# N_FET.net
KiCad netlist of a schematic drawn in Altium Designer
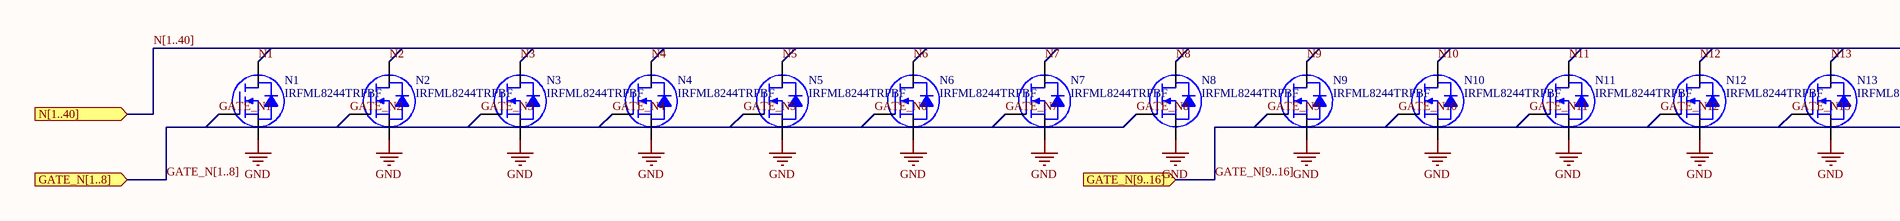
[diagram p0: N_FET.SchDoc, left]
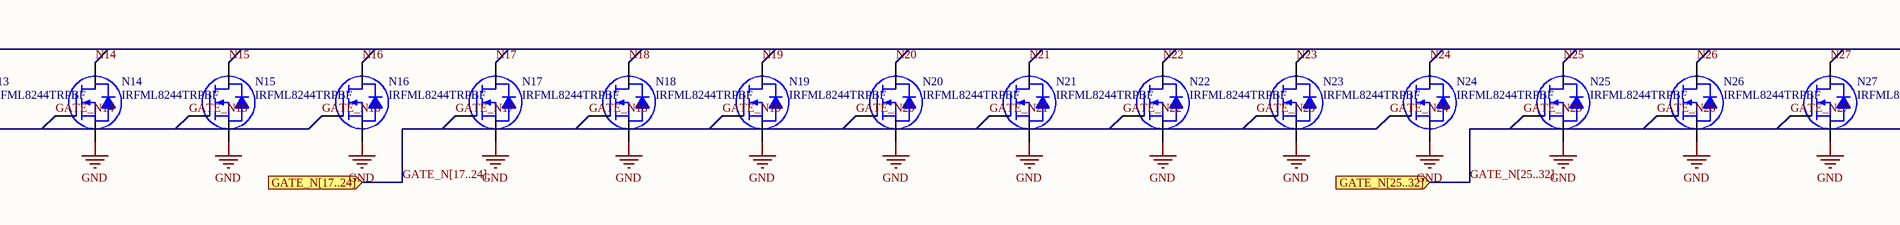
[diagram p1: N_FET.SchDoc, middle]
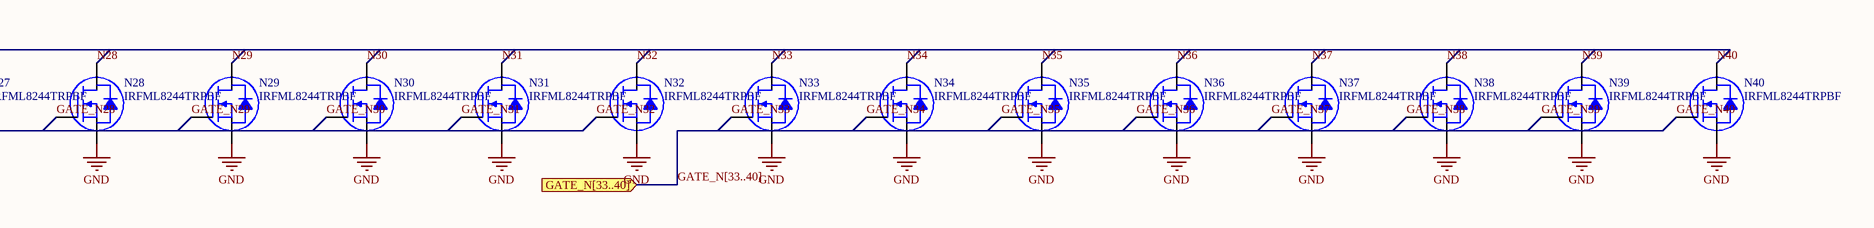
[diagram p2: N_FET.SchDoc, right]

(export (version "E")
  (design (tool "Eeschema 10.0.6"))
  (components
    (comp (ref "N1")
      (value "IRFML8244TRPBF")
      (footprint "INFINEON SOT-23-3")
      (description "MOSFET N-CH 25V 5.8A SOT23")
      (fields (field (name "MANUFACTURER") "Infineon Technologies"))
      (libsource (lib "Celestial Library Database") (part "INFINEON MOSFET N-CH SOT-23-3"))
    )
    (comp (ref "N2")
      (value "IRFML8244TRPBF")
      (footprint "INFINEON SOT-23-3")
      (description "MOSFET N-CH 25V 5.8A SOT23")
      (fields (field (name "MANUFACTURER") "Infineon Technologies"))
      (libsource (lib "Celestial Library Database") (part "INFINEON MOSFET N-CH SOT-23-3"))
    )
    (comp (ref "N3")
      (value "IRFML8244TRPBF")
      (footprint "INFINEON SOT-23-3")
      (description "MOSFET N-CH 25V 5.8A SOT23")
      (fields (field (name "MANUFACTURER") "Infineon Technologies"))
      (libsource (lib "Celestial Library Database") (part "INFINEON MOSFET N-CH SOT-23-3"))
    )
    (comp (ref "N4")
      (value "IRFML8244TRPBF")
      (footprint "INFINEON SOT-23-3")
      (description "MOSFET N-CH 25V 5.8A SOT23")
      (fields (field (name "MANUFACTURER") "Infineon Technologies"))
      (libsource (lib "Celestial Library Database") (part "INFINEON MOSFET N-CH SOT-23-3"))
    )
    (comp (ref "N5")
      (value "IRFML8244TRPBF")
      (footprint "INFINEON SOT-23-3")
      (description "MOSFET N-CH 25V 5.8A SOT23")
      (fields (field (name "MANUFACTURER") "Infineon Technologies"))
      (libsource (lib "Celestial Library Database") (part "INFINEON MOSFET N-CH SOT-23-3"))
    )
    (comp (ref "N6")
      (value "IRFML8244TRPBF")
      (footprint "INFINEON SOT-23-3")
      (description "MOSFET N-CH 25V 5.8A SOT23")
      (fields (field (name "MANUFACTURER") "Infineon Technologies"))
      (libsource (lib "Celestial Library Database") (part "INFINEON MOSFET N-CH SOT-23-3"))
    )
    (comp (ref "N7")
      (value "IRFML8244TRPBF")
      (footprint "INFINEON SOT-23-3")
      (description "MOSFET N-CH 25V 5.8A SOT23")
      (fields (field (name "MANUFACTURER") "Infineon Technologies"))
      (libsource (lib "Celestial Library Database") (part "INFINEON MOSFET N-CH SOT-23-3"))
    )
    (comp (ref "N8")
      (value "IRFML8244TRPBF")
      (footprint "INFINEON SOT-23-3")
      (description "MOSFET N-CH 25V 5.8A SOT23")
      (fields (field (name "MANUFACTURER") "Infineon Technologies"))
      (libsource (lib "Celestial Library Database") (part "INFINEON MOSFET N-CH SOT-23-3"))
    )
    (comp (ref "N9")
      (value "IRFML8244TRPBF")
      (footprint "INFINEON SOT-23-3")
      (description "MOSFET N-CH 25V 5.8A SOT23")
      (fields (field (name "MANUFACTURER") "Infineon Technologies"))
      (libsource (lib "Celestial Library Database") (part "INFINEON MOSFET N-CH SOT-23-3"))
    )
    (comp (ref "N10")
      (value "IRFML8244TRPBF")
      (footprint "INFINEON SOT-23-3")
      (description "MOSFET N-CH 25V 5.8A SOT23")
      (fields (field (name "MANUFACTURER") "Infineon Technologies"))
      (libsource (lib "Celestial Library Database") (part "INFINEON MOSFET N-CH SOT-23-3"))
    )
    (comp (ref "N11")
      (value "IRFML8244TRPBF")
      (footprint "INFINEON SOT-23-3")
      (description "MOSFET N-CH 25V 5.8A SOT23")
      (fields (field (name "MANUFACTURER") "Infineon Technologies"))
      (libsource (lib "Celestial Library Database") (part "INFINEON MOSFET N-CH SOT-23-3"))
    )
    (comp (ref "N12")
      (value "IRFML8244TRPBF")
      (footprint "INFINEON SOT-23-3")
      (description "MOSFET N-CH 25V 5.8A SOT23")
      (fields (field (name "MANUFACTURER") "Infineon Technologies"))
      (libsource (lib "Celestial Library Database") (part "INFINEON MOSFET N-CH SOT-23-3"))
    )
    (comp (ref "N13")
      (value "IRFML8244TRPBF")
      (footprint "INFINEON SOT-23-3")
      (description "MOSFET N-CH 25V 5.8A SOT23")
      (fields (field (name "MANUFACTURER") "Infineon Technologies"))
      (libsource (lib "Celestial Library Database") (part "INFINEON MOSFET N-CH SOT-23-3"))
    )
    (comp (ref "N14")
      (value "IRFML8244TRPBF")
      (footprint "INFINEON SOT-23-3")
      (description "MOSFET N-CH 25V 5.8A SOT23")
      (fields (field (name "MANUFACTURER") "Infineon Technologies"))
      (libsource (lib "Celestial Library Database") (part "INFINEON MOSFET N-CH SOT-23-3"))
    )
    (comp (ref "N15")
      (value "IRFML8244TRPBF")
      (footprint "INFINEON SOT-23-3")
      (description "MOSFET N-CH 25V 5.8A SOT23")
      (fields (field (name "MANUFACTURER") "Infineon Technologies"))
      (libsource (lib "Celestial Library Database") (part "INFINEON MOSFET N-CH SOT-23-3"))
    )
    (comp (ref "N16")
      (value "IRFML8244TRPBF")
      (footprint "INFINEON SOT-23-3")
      (description "MOSFET N-CH 25V 5.8A SOT23")
      (fields (field (name "MANUFACTURER") "Infineon Technologies"))
      (libsource (lib "Celestial Library Database") (part "INFINEON MOSFET N-CH SOT-23-3"))
    )
    (comp (ref "N17")
      (value "IRFML8244TRPBF")
      (footprint "INFINEON SOT-23-3")
      (description "MOSFET N-CH 25V 5.8A SOT23")
      (fields (field (name "MANUFACTURER") "Infineon Technologies"))
      (libsource (lib "Celestial Library Database") (part "INFINEON MOSFET N-CH SOT-23-3"))
    )
    (comp (ref "N18")
      (value "IRFML8244TRPBF")
      (footprint "INFINEON SOT-23-3")
      (description "MOSFET N-CH 25V 5.8A SOT23")
      (fields (field (name "MANUFACTURER") "Infineon Technologies"))
      (libsource (lib "Celestial Library Database") (part "INFINEON MOSFET N-CH SOT-23-3"))
    )
    (comp (ref "N19")
      (value "IRFML8244TRPBF")
      (footprint "INFINEON SOT-23-3")
      (description "MOSFET N-CH 25V 5.8A SOT23")
      (fields (field (name "MANUFACTURER") "Infineon Technologies"))
      (libsource (lib "Celestial Library Database") (part "INFINEON MOSFET N-CH SOT-23-3"))
    )
    (comp (ref "N20")
      (value "IRFML8244TRPBF")
      (footprint "INFINEON SOT-23-3")
      (description "MOSFET N-CH 25V 5.8A SOT23")
      (fields (field (name "MANUFACTURER") "Infineon Technologies"))
      (libsource (lib "Celestial Library Database") (part "INFINEON MOSFET N-CH SOT-23-3"))
    )
    (comp (ref "N21")
      (value "IRFML8244TRPBF")
      (footprint "INFINEON SOT-23-3")
      (description "MOSFET N-CH 25V 5.8A SOT23")
      (fields (field (name "MANUFACTURER") "Infineon Technologies"))
      (libsource (lib "Celestial Library Database") (part "INFINEON MOSFET N-CH SOT-23-3"))
    )
    (comp (ref "N22")
      (value "IRFML8244TRPBF")
      (footprint "INFINEON SOT-23-3")
      (description "MOSFET N-CH 25V 5.8A SOT23")
      (fields (field (name "MANUFACTURER") "Infineon Technologies"))
      (libsource (lib "Celestial Library Database") (part "INFINEON MOSFET N-CH SOT-23-3"))
    )
    (comp (ref "N23")
      (value "IRFML8244TRPBF")
      (footprint "INFINEON SOT-23-3")
      (description "MOSFET N-CH 25V 5.8A SOT23")
      (fields (field (name "MANUFACTURER") "Infineon Technologies"))
      (libsource (lib "Celestial Library Database") (part "INFINEON MOSFET N-CH SOT-23-3"))
    )
    (comp (ref "N24")
      (value "IRFML8244TRPBF")
      (footprint "INFINEON SOT-23-3")
      (description "MOSFET N-CH 25V 5.8A SOT23")
      (fields (field (name "MANUFACTURER") "Infineon Technologies"))
      (libsource (lib "Celestial Library Database") (part "INFINEON MOSFET N-CH SOT-23-3"))
    )
    (comp (ref "N25")
      (value "IRFML8244TRPBF")
      (footprint "INFINEON SOT-23-3")
      (description "MOSFET N-CH 25V 5.8A SOT23")
      (fields (field (name "MANUFACTURER") "Infineon Technologies"))
      (libsource (lib "Celestial Library Database") (part "INFINEON MOSFET N-CH SOT-23-3"))
    )
    (comp (ref "N26")
      (value "IRFML8244TRPBF")
      (footprint "INFINEON SOT-23-3")
      (description "MOSFET N-CH 25V 5.8A SOT23")
      (fields (field (name "MANUFACTURER") "Infineon Technologies"))
      (libsource (lib "Celestial Library Database") (part "INFINEON MOSFET N-CH SOT-23-3"))
    )
    (comp (ref "N27")
      (value "IRFML8244TRPBF")
      (footprint "INFINEON SOT-23-3")
      (description "MOSFET N-CH 25V 5.8A SOT23")
      (fields (field (name "MANUFACTURER") "Infineon Technologies"))
      (libsource (lib "Celestial Library Database") (part "INFINEON MOSFET N-CH SOT-23-3"))
    )
    (comp (ref "N28")
      (value "IRFML8244TRPBF")
      (footprint "INFINEON SOT-23-3")
      (description "MOSFET N-CH 25V 5.8A SOT23")
      (fields (field (name "MANUFACTURER") "Infineon Technologies"))
      (libsource (lib "Celestial Library Database") (part "INFINEON MOSFET N-CH SOT-23-3"))
    )
    (comp (ref "N29")
      (value "IRFML8244TRPBF")
      (footprint "INFINEON SOT-23-3")
      (description "MOSFET N-CH 25V 5.8A SOT23")
      (fields (field (name "MANUFACTURER") "Infineon Technologies"))
      (libsource (lib "Celestial Library Database") (part "INFINEON MOSFET N-CH SOT-23-3"))
    )
    (comp (ref "N30")
      (value "IRFML8244TRPBF")
      (footprint "INFINEON SOT-23-3")
      (description "MOSFET N-CH 25V 5.8A SOT23")
      (fields (field (name "MANUFACTURER") "Infineon Technologies"))
      (libsource (lib "Celestial Library Database") (part "INFINEON MOSFET N-CH SOT-23-3"))
    )
    (comp (ref "N31")
      (value "IRFML8244TRPBF")
      (footprint "INFINEON SOT-23-3")
      (description "MOSFET N-CH 25V 5.8A SOT23")
      (fields (field (name "MANUFACTURER") "Infineon Technologies"))
      (libsource (lib "Celestial Library Database") (part "INFINEON MOSFET N-CH SOT-23-3"))
    )
    (comp (ref "N32")
      (value "IRFML8244TRPBF")
      (footprint "INFINEON SOT-23-3")
      (description "MOSFET N-CH 25V 5.8A SOT23")
      (fields (field (name "MANUFACTURER") "Infineon Technologies"))
      (libsource (lib "Celestial Library Database") (part "INFINEON MOSFET N-CH SOT-23-3"))
    )
    (comp (ref "N33")
      (value "IRFML8244TRPBF")
      (footprint "INFINEON SOT-23-3")
      (description "MOSFET N-CH 25V 5.8A SOT23")
      (fields (field (name "MANUFACTURER") "Infineon Technologies"))
      (libsource (lib "Celestial Library Database") (part "INFINEON MOSFET N-CH SOT-23-3"))
    )
    (comp (ref "N34")
      (value "IRFML8244TRPBF")
      (footprint "INFINEON SOT-23-3")
      (description "MOSFET N-CH 25V 5.8A SOT23")
      (fields (field (name "MANUFACTURER") "Infineon Technologies"))
      (libsource (lib "Celestial Library Database") (part "INFINEON MOSFET N-CH SOT-23-3"))
    )
    (comp (ref "N35")
      (value "IRFML8244TRPBF")
      (footprint "INFINEON SOT-23-3")
      (description "MOSFET N-CH 25V 5.8A SOT23")
      (fields (field (name "MANUFACTURER") "Infineon Technologies"))
      (libsource (lib "Celestial Library Database") (part "INFINEON MOSFET N-CH SOT-23-3"))
    )
    (comp (ref "N36")
      (value "IRFML8244TRPBF")
      (footprint "INFINEON SOT-23-3")
      (description "MOSFET N-CH 25V 5.8A SOT23")
      (fields (field (name "MANUFACTURER") "Infineon Technologies"))
      (libsource (lib "Celestial Library Database") (part "INFINEON MOSFET N-CH SOT-23-3"))
    )
    (comp (ref "N37")
      (value "IRFML8244TRPBF")
      (footprint "INFINEON SOT-23-3")
      (description "MOSFET N-CH 25V 5.8A SOT23")
      (fields (field (name "MANUFACTURER") "Infineon Technologies"))
      (libsource (lib "Celestial Library Database") (part "INFINEON MOSFET N-CH SOT-23-3"))
    )
    (comp (ref "N38")
      (value "IRFML8244TRPBF")
      (footprint "INFINEON SOT-23-3")
      (description "MOSFET N-CH 25V 5.8A SOT23")
      (fields (field (name "MANUFACTURER") "Infineon Technologies"))
      (libsource (lib "Celestial Library Database") (part "INFINEON MOSFET N-CH SOT-23-3"))
    )
    (comp (ref "N39")
      (value "IRFML8244TRPBF")
      (footprint "INFINEON SOT-23-3")
      (description "MOSFET N-CH 25V 5.8A SOT23")
      (fields (field (name "MANUFACTURER") "Infineon Technologies"))
      (libsource (lib "Celestial Library Database") (part "INFINEON MOSFET N-CH SOT-23-3"))
    )
    (comp (ref "N40")
      (value "IRFML8244TRPBF")
      (footprint "INFINEON SOT-23-3")
      (description "MOSFET N-CH 25V 5.8A SOT23")
      (fields (field (name "MANUFACTURER") "Infineon Technologies"))
      (libsource (lib "Celestial Library Database") (part "INFINEON MOSFET N-CH SOT-23-3"))
    )
  )
  (nets
    (net (code "1") (name "/GATE_N1") (class "Default")
      (node (ref "N1") (pin "1") (pinfunction "G_1") (pintype "passive"))
    )
    (net (code "2") (name "/GATE_N2") (class "Default")
      (node (ref "N2") (pin "1") (pinfunction "G_1") (pintype "passive"))
    )
    (net (code "3") (name "/GATE_N3") (class "Default")
      (node (ref "N3") (pin "1") (pinfunction "G_1") (pintype "passive"))
    )
    (net (code "4") (name "/GATE_N4") (class "Default")
      (node (ref "N4") (pin "1") (pinfunction "G_1") (pintype "passive"))
    )
    (net (code "5") (name "/GATE_N5") (class "Default")
      (node (ref "N5") (pin "1") (pinfunction "G_1") (pintype "passive"))
    )
    (net (code "6") (name "/GATE_N6") (class "Default")
      (node (ref "N6") (pin "1") (pinfunction "G_1") (pintype "passive"))
    )
    (net (code "7") (name "/GATE_N7") (class "Default")
      (node (ref "N7") (pin "1") (pinfunction "G_1") (pintype "passive"))
    )
    (net (code "8") (name "/GATE_N8") (class "Default")
      (node (ref "N8") (pin "1") (pinfunction "G_1") (pintype "passive"))
    )
    (net (code "9") (name "/GATE_N9") (class "Default")
      (node (ref "N9") (pin "1") (pinfunction "G_1") (pintype "passive"))
    )
    (net (code "10") (name "/GATE_N10") (class "Default")
      (node (ref "N10") (pin "1") (pinfunction "G_1") (pintype "passive"))
    )
    (net (code "11") (name "/GATE_N11") (class "Default")
      (node (ref "N11") (pin "1") (pinfunction "G_1") (pintype "passive"))
    )
    (net (code "12") (name "/GATE_N12") (class "Default")
      (node (ref "N12") (pin "1") (pinfunction "G_1") (pintype "passive"))
    )
    (net (code "13") (name "/GATE_N13") (class "Default")
      (node (ref "N13") (pin "1") (pinfunction "G_1") (pintype "passive"))
    )
    (net (code "14") (name "/GATE_N14") (class "Default")
      (node (ref "N14") (pin "1") (pinfunction "G_1") (pintype "passive"))
    )
    (net (code "15") (name "/GATE_N15") (class "Default")
      (node (ref "N15") (pin "1") (pinfunction "G_1") (pintype "passive"))
    )
    (net (code "16") (name "/GATE_N16") (class "Default")
      (node (ref "N16") (pin "1") (pinfunction "G_1") (pintype "passive"))
    )
    (net (code "17") (name "/GATE_N17") (class "Default")
      (node (ref "N17") (pin "1") (pinfunction "G_1") (pintype "passive"))
    )
    (net (code "18") (name "/GATE_N18") (class "Default")
      (node (ref "N18") (pin "1") (pinfunction "G_1") (pintype "passive"))
    )
    (net (code "19") (name "/GATE_N19") (class "Default")
      (node (ref "N19") (pin "1") (pinfunction "G_1") (pintype "passive"))
    )
    (net (code "20") (name "/GATE_N20") (class "Default")
      (node (ref "N20") (pin "1") (pinfunction "G_1") (pintype "passive"))
    )
    (net (code "21") (name "/GATE_N21") (class "Default")
      (node (ref "N21") (pin "1") (pinfunction "G_1") (pintype "passive"))
    )
    (net (code "22") (name "/GATE_N22") (class "Default")
      (node (ref "N22") (pin "1") (pinfunction "G_1") (pintype "passive"))
    )
    (net (code "23") (name "/GATE_N23") (class "Default")
      (node (ref "N23") (pin "1") (pinfunction "G_1") (pintype "passive"))
    )
    (net (code "24") (name "/GATE_N24") (class "Default")
      (node (ref "N24") (pin "1") (pinfunction "G_1") (pintype "passive"))
    )
    (net (code "25") (name "/GATE_N25") (class "Default")
      (node (ref "N25") (pin "1") (pinfunction "G_1") (pintype "passive"))
    )
    (net (code "26") (name "/GATE_N26") (class "Default")
      (node (ref "N26") (pin "1") (pinfunction "G_1") (pintype "passive"))
    )
    (net (code "27") (name "/GATE_N27") (class "Default")
      (node (ref "N27") (pin "1") (pinfunction "G_1") (pintype "passive"))
    )
    (net (code "28") (name "/GATE_N28") (class "Default")
      (node (ref "N28") (pin "1") (pinfunction "G_1") (pintype "passive"))
    )
    (net (code "29") (name "/GATE_N29") (class "Default")
      (node (ref "N29") (pin "1") (pinfunction "G_1") (pintype "passive"))
    )
    (net (code "30") (name "/GATE_N30") (class "Default")
      (node (ref "N30") (pin "1") (pinfunction "G_1") (pintype "passive"))
    )
    (net (code "31") (name "/GATE_N31") (class "Default")
      (node (ref "N31") (pin "1") (pinfunction "G_1") (pintype "passive"))
    )
    (net (code "32") (name "/GATE_N32") (class "Default")
      (node (ref "N32") (pin "1") (pinfunction "G_1") (pintype "passive"))
    )
    (net (code "33") (name "/GATE_N33") (class "Default")
      (node (ref "N33") (pin "1") (pinfunction "G_1") (pintype "passive"))
    )
    (net (code "34") (name "/GATE_N34") (class "Default")
      (node (ref "N34") (pin "1") (pinfunction "G_1") (pintype "passive"))
    )
    (net (code "35") (name "/GATE_N35") (class "Default")
      (node (ref "N35") (pin "1") (pinfunction "G_1") (pintype "passive"))
    )
    (net (code "36") (name "/GATE_N36") (class "Default")
      (node (ref "N36") (pin "1") (pinfunction "G_1") (pintype "passive"))
    )
    (net (code "37") (name "/GATE_N37") (class "Default")
      (node (ref "N37") (pin "1") (pinfunction "G_1") (pintype "passive"))
    )
    (net (code "38") (name "/GATE_N38") (class "Default")
      (node (ref "N38") (pin "1") (pinfunction "G_1") (pintype "passive"))
    )
    (net (code "39") (name "/GATE_N39") (class "Default")
      (node (ref "N39") (pin "1") (pinfunction "G_1") (pintype "passive"))
    )
    (net (code "40") (name "/GATE_N40") (class "Default")
      (node (ref "N40") (pin "1") (pinfunction "G_1") (pintype "passive"))
    )
    (net (code "46") (name "/N1") (class "Default")
      (node (ref "N1") (pin "2") (pinfunction "D_2") (pintype "passive"))
    )
    (net (code "47") (name "/N2") (class "Default")
      (node (ref "N2") (pin "2") (pinfunction "D_2") (pintype "passive"))
    )
    (net (code "48") (name "/N3") (class "Default")
      (node (ref "N3") (pin "2") (pinfunction "D_2") (pintype "passive"))
    )
    (net (code "49") (name "/N4") (class "Default")
      (node (ref "N4") (pin "2") (pinfunction "D_2") (pintype "passive"))
    )
    (net (code "50") (name "/N5") (class "Default")
      (node (ref "N5") (pin "2") (pinfunction "D_2") (pintype "passive"))
    )
    (net (code "51") (name "/N6") (class "Default")
      (node (ref "N6") (pin "2") (pinfunction "D_2") (pintype "passive"))
    )
    (net (code "52") (name "/N7") (class "Default")
      (node (ref "N7") (pin "2") (pinfunction "D_2") (pintype "passive"))
    )
    (net (code "53") (name "/N8") (class "Default")
      (node (ref "N8") (pin "2") (pinfunction "D_2") (pintype "passive"))
    )
    (net (code "54") (name "/N9") (class "Default")
      (node (ref "N9") (pin "2") (pinfunction "D_2") (pintype "passive"))
    )
    (net (code "55") (name "/N10") (class "Default")
      (node (ref "N10") (pin "2") (pinfunction "D_2") (pintype "passive"))
    )
    (net (code "56") (name "/N11") (class "Default")
      (node (ref "N11") (pin "2") (pinfunction "D_2") (pintype "passive"))
    )
    (net (code "57") (name "/N12") (class "Default")
      (node (ref "N12") (pin "2") (pinfunction "D_2") (pintype "passive"))
    )
    (net (code "58") (name "/N13") (class "Default")
      (node (ref "N13") (pin "2") (pinfunction "D_2") (pintype "passive"))
    )
    (net (code "59") (name "/N14") (class "Default")
      (node (ref "N14") (pin "2") (pinfunction "D_2") (pintype "passive"))
    )
    (net (code "60") (name "/N15") (class "Default")
      (node (ref "N15") (pin "2") (pinfunction "D_2") (pintype "passive"))
    )
    (net (code "61") (name "/N16") (class "Default")
      (node (ref "N16") (pin "2") (pinfunction "D_2") (pintype "passive"))
    )
    (net (code "62") (name "/N17") (class "Default")
      (node (ref "N17") (pin "2") (pinfunction "D_2") (pintype "passive"))
    )
    (net (code "63") (name "/N18") (class "Default")
      (node (ref "N18") (pin "2") (pinfunction "D_2") (pintype "passive"))
    )
    (net (code "64") (name "/N19") (class "Default")
      (node (ref "N19") (pin "2") (pinfunction "D_2") (pintype "passive"))
    )
    (net (code "65") (name "/N20") (class "Default")
      (node (ref "N20") (pin "2") (pinfunction "D_2") (pintype "passive"))
    )
    (net (code "66") (name "/N21") (class "Default")
      (node (ref "N21") (pin "2") (pinfunction "D_2") (pintype "passive"))
    )
    (net (code "67") (name "/N22") (class "Default")
      (node (ref "N22") (pin "2") (pinfunction "D_2") (pintype "passive"))
    )
    (net (code "68") (name "/N23") (class "Default")
      (node (ref "N23") (pin "2") (pinfunction "D_2") (pintype "passive"))
    )
    (net (code "69") (name "/N24") (class "Default")
      (node (ref "N24") (pin "2") (pinfunction "D_2") (pintype "passive"))
    )
    (net (code "70") (name "/N25") (class "Default")
      (node (ref "N25") (pin "2") (pinfunction "D_2") (pintype "passive"))
    )
    (net (code "71") (name "/N26") (class "Default")
      (node (ref "N26") (pin "2") (pinfunction "D_2") (pintype "passive"))
    )
    (net (code "72") (name "/N27") (class "Default")
      (node (ref "N27") (pin "2") (pinfunction "D_2") (pintype "passive"))
    )
    (net (code "73") (name "/N28") (class "Default")
      (node (ref "N28") (pin "2") (pinfunction "D_2") (pintype "passive"))
    )
    (net (code "74") (name "/N29") (class "Default")
      (node (ref "N29") (pin "2") (pinfunction "D_2") (pintype "passive"))
    )
    (net (code "75") (name "/N30") (class "Default")
      (node (ref "N30") (pin "2") (pinfunction "D_2") (pintype "passive"))
    )
    (net (code "76") (name "/N31") (class "Default")
      (node (ref "N31") (pin "2") (pinfunction "D_2") (pintype "passive"))
    )
    (net (code "77") (name "/N32") (class "Default")
      (node (ref "N32") (pin "2") (pinfunction "D_2") (pintype "passive"))
    )
    (net (code "78") (name "/N33") (class "Default")
      (node (ref "N33") (pin "2") (pinfunction "D_2") (pintype "passive"))
    )
    (net (code "79") (name "/N34") (class "Default")
      (node (ref "N34") (pin "2") (pinfunction "D_2") (pintype "passive"))
    )
    (net (code "80") (name "/N35") (class "Default")
      (node (ref "N35") (pin "2") (pinfunction "D_2") (pintype "passive"))
    )
    (net (code "81") (name "/N36") (class "Default")
      (node (ref "N36") (pin "2") (pinfunction "D_2") (pintype "passive"))
    )
    (net (code "82") (name "/N37") (class "Default")
      (node (ref "N37") (pin "2") (pinfunction "D_2") (pintype "passive"))
    )
    (net (code "83") (name "/N38") (class "Default")
      (node (ref "N38") (pin "2") (pinfunction "D_2") (pintype "passive"))
    )
    (net (code "84") (name "/N39") (class "Default")
      (node (ref "N39") (pin "2") (pinfunction "D_2") (pintype "passive"))
    )
    (net (code "85") (name "/N40") (class "Default")
      (node (ref "N40") (pin "2") (pinfunction "D_2") (pintype "passive"))
    )
    (net (code "87") (name "GND") (class "Default")
      (node (ref "N1") (pin "3") (pinfunction "S_3") (pintype "passive"))
      (node (ref "N10") (pin "3") (pinfunction "S_3") (pintype "passive"))
      (node (ref "N11") (pin "3") (pinfunction "S_3") (pintype "passive"))
      (node (ref "N12") (pin "3") (pinfunction "S_3") (pintype "passive"))
      (node (ref "N13") (pin "3") (pinfunction "S_3") (pintype "passive"))
      (node (ref "N14") (pin "3") (pinfunction "S_3") (pintype "passive"))
      (node (ref "N15") (pin "3") (pinfunction "S_3") (pintype "passive"))
      (node (ref "N16") (pin "3") (pinfunction "S_3") (pintype "passive"))
      (node (ref "N17") (pin "3") (pinfunction "S_3") (pintype "passive"))
      (node (ref "N18") (pin "3") (pinfunction "S_3") (pintype "passive"))
      (node (ref "N19") (pin "3") (pinfunction "S_3") (pintype "passive"))
      (node (ref "N2") (pin "3") (pinfunction "S_3") (pintype "passive"))
      (node (ref "N20") (pin "3") (pinfunction "S_3") (pintype "passive"))
      (node (ref "N21") (pin "3") (pinfunction "S_3") (pintype "passive"))
      (node (ref "N22") (pin "3") (pinfunction "S_3") (pintype "passive"))
      (node (ref "N23") (pin "3") (pinfunction "S_3") (pintype "passive"))
      (node (ref "N24") (pin "3") (pinfunction "S_3") (pintype "passive"))
      (node (ref "N25") (pin "3") (pinfunction "S_3") (pintype "passive"))
      (node (ref "N26") (pin "3") (pinfunction "S_3") (pintype "passive"))
      (node (ref "N27") (pin "3") (pinfunction "S_3") (pintype "passive"))
      (node (ref "N28") (pin "3") (pinfunction "S_3") (pintype "passive"))
      (node (ref "N29") (pin "3") (pinfunction "S_3") (pintype "passive"))
      (node (ref "N3") (pin "3") (pinfunction "S_3") (pintype "passive"))
      (node (ref "N30") (pin "3") (pinfunction "S_3") (pintype "passive"))
      (node (ref "N31") (pin "3") (pinfunction "S_3") (pintype "passive"))
      (node (ref "N32") (pin "3") (pinfunction "S_3") (pintype "passive"))
      (node (ref "N33") (pin "3") (pinfunction "S_3") (pintype "passive"))
      (node (ref "N34") (pin "3") (pinfunction "S_3") (pintype "passive"))
      (node (ref "N35") (pin "3") (pinfunction "S_3") (pintype "passive"))
      (node (ref "N36") (pin "3") (pinfunction "S_3") (pintype "passive"))
      (node (ref "N37") (pin "3") (pinfunction "S_3") (pintype "passive"))
      (node (ref "N38") (pin "3") (pinfunction "S_3") (pintype "passive"))
      (node (ref "N39") (pin "3") (pinfunction "S_3") (pintype "passive"))
      (node (ref "N4") (pin "3") (pinfunction "S_3") (pintype "passive"))
      (node (ref "N40") (pin "3") (pinfunction "S_3") (pintype "passive"))
      (node (ref "N5") (pin "3") (pinfunction "S_3") (pintype "passive"))
      (node (ref "N6") (pin "3") (pinfunction "S_3") (pintype "passive"))
      (node (ref "N7") (pin "3") (pinfunction "S_3") (pintype "passive"))
      (node (ref "N8") (pin "3") (pinfunction "S_3") (pintype "passive"))
      (node (ref "N9") (pin "3") (pinfunction "S_3") (pintype "passive"))
    )
  )
)
